# Relay.net
KiCad netlist of a schematic drawn in Altium Designer
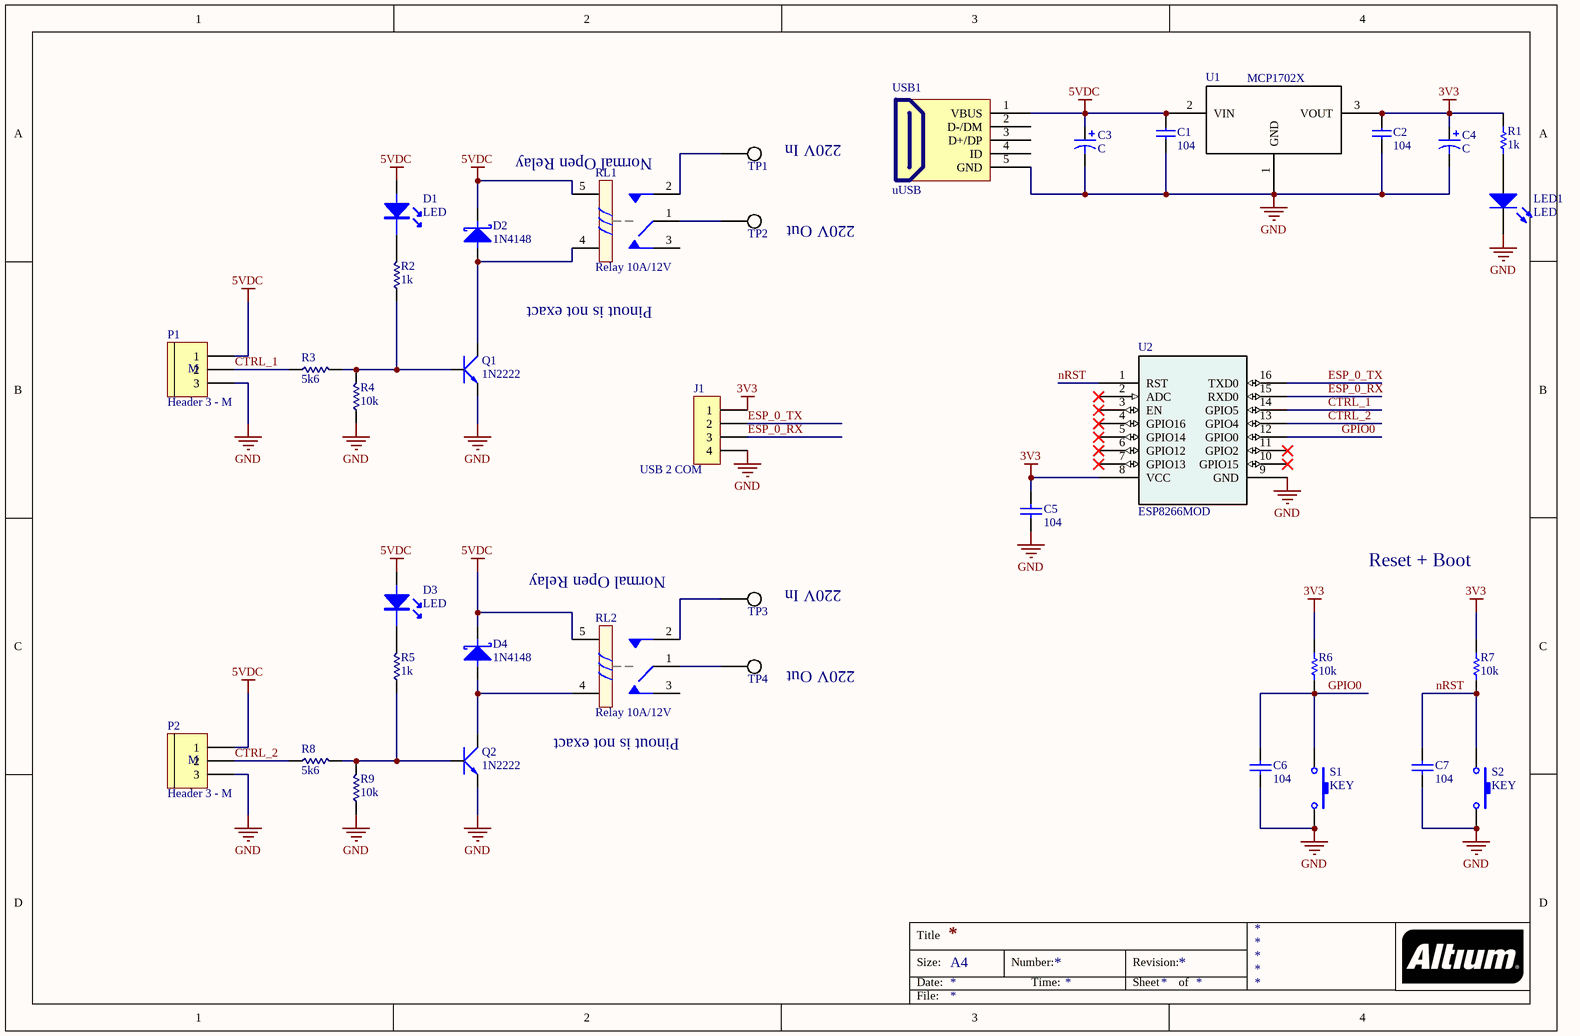
[diagram p0: Relay.SchDoc]

(export (version "E")
  (design (tool "Eeschema 10.0.6"))
  (components
    (comp (ref "C1")
      (value "104")
      (footprint "C0603")
      (description "Capacitor, X7R, ±10%")
      (fields (field (name "PART NUMBER") "C0402-1n0") (field (name "PUBLISHER") "Nordic Semiconductor"))
      (libsource (lib "Nordic Passive DB") (part "CAP"))
    )
    (comp (ref "C2")
      (value "104")
      (footprint "C0603")
      (description "Capacitor, X7R, ±10%")
      (fields (field (name "PART NUMBER") "C0402-1n0") (field (name "PUBLISHER") "Nordic Semiconductor"))
      (libsource (lib "Nordic Passive DB") (part "CAP"))
    )
    (comp (ref "C3")
      (value "C")
      (footprint "3216-18")
      (description "Cap 100uF/35V - 470uF/16V")
      (libsource (lib "Capacitor") (part "CAP POL"))
    )
    (comp (ref "C4")
      (value "C")
      (footprint "3216-18")
      (description "Cap 100uF/35V - 470uF/16V")
      (libsource (lib "Capacitor") (part "CAP POL"))
    )
    (comp (ref "C5")
      (value "104")
      (footprint "C0603")
      (description "Capacitor")
      (fields (field (name "PUBLISHER") "Altium Limited"))
      (libsource (lib "VTEKLib") (part "Cap Ceramic"))
    )
    (comp (ref "C6")
      (value "104")
      (footprint "C0603")
      (description "Capacitor")
      (fields (field (name "PUBLISHER") "Altium Limited"))
      (libsource (lib "VTEKLib") (part "Cap Ceramic"))
    )
    (comp (ref "C7")
      (value "104")
      (footprint "C0603")
      (description "Capacitor")
      (fields (field (name "PUBLISHER") "Altium Limited"))
      (libsource (lib "VTEKLib") (part "Cap Ceramic"))
    )
    (comp (ref "D1") (value "LED") (footprint "CAP10UF") (libsource (lib "Cty1") (part "LED")))
    (comp (ref "D2")
      (value "1N4148")
      (footprint "diode")
      (description "Schottky Diode")
      (libsource (lib "Cty1") (part "1N4148"))
    )
    (comp (ref "D3") (value "LED") (footprint "CAP10UF") (libsource (lib "Cty1") (part "LED")))
    (comp (ref "D4")
      (value "1N4148")
      (footprint "diode")
      (description "Schottky Diode")
      (libsource (lib "Cty1") (part "1N4148"))
    )
    (comp (ref "J1")
      (value "USB 2 COM")
      (footprint "HDR1X4")
      (description "Connector")
      (libsource (lib "Connecter") (part "CON4"))
    )
    (comp (ref "LED1")
      (value "LED")
      (footprint "LED0805")
      (description "Typical INFRARED GaAs LED")
      (fields (field (name "PUBLISHER") "Altium Limited"))
      (libsource (lib "VTEKLib") (part "LED"))
    )
    (comp (ref "P1")
      (value "Header 3 - M")
      (footprint "Medium - Header 3")
      (description "Header, 3-Pin, Medium")
      (fields (field (name "PUBLISHER") "Altium Limited"))
      (libsource (lib "Connecter") (part "Header 3 - M"))
    )
    (comp (ref "P2")
      (value "Header 3 - M")
      (footprint "Medium - Header 3")
      (description "Header, 3-Pin, Medium")
      (fields (field (name "PUBLISHER") "Altium Limited"))
      (libsource (lib "Connecter") (part "Header 3 - M"))
    )
    (comp (ref "Q1")
      (value "1N2222")
      (footprint "SOT23A")
      (description "NPN switching transistor  40V 600mA SOT23")
      (fields (field (name "MANUFACTURER") "Fairchild"))
      (libsource (lib "Cty1") (part "MMBT2222A"))
    )
    (comp (ref "Q2")
      (value "1N2222")
      (footprint "SOT23A")
      (description "NPN switching transistor  40V 600mA SOT23")
      (fields (field (name "MANUFACTURER") "Fairchild"))
      (libsource (lib "Cty1") (part "MMBT2222A"))
    )
    (comp (ref "R1")
      (value "1k")
      (footprint "R0603-2")
      (fields (field (name "PUBLISHER") "Altium Limited"))
      (libsource (lib "VTEKLib") (part "RES"))
    )
    (comp (ref "R2")
      (value "1k")
      (footprint "R1/4W")
      (description "Resistor 1/4W")
      (libsource (lib "Cty1") (part "R1/4W"))
    )
    (comp (ref "R3")
      (value "5k6")
      (footprint "R1/4W")
      (description "Resistor 1/4W")
      (libsource (lib "Cty1") (part "R1/4W"))
    )
    (comp (ref "R4")
      (value "10k")
      (footprint "R1/4W")
      (description "Resistor 1/4W")
      (libsource (lib "Cty1") (part "R1/4W"))
    )
    (comp (ref "R5")
      (value "1k")
      (footprint "R1/4W")
      (description "Resistor 1/4W")
      (libsource (lib "Cty1") (part "R1/4W"))
    )
    (comp (ref "R6")
      (value "10k")
      (footprint "R0603-2")
      (fields (field (name "PUBLISHER") "Altium Limited"))
      (libsource (lib "VTEKLib") (part "RES"))
    )
    (comp (ref "R7")
      (value "10k")
      (footprint "R0603-2")
      (fields (field (name "PUBLISHER") "Altium Limited"))
      (libsource (lib "VTEKLib") (part "RES"))
    )
    (comp (ref "R8")
      (value "5k6")
      (footprint "R1/4W")
      (description "Resistor 1/4W")
      (libsource (lib "Cty1") (part "R1/4W"))
    )
    (comp (ref "R9")
      (value "10k")
      (footprint "R1/4W")
      (description "Resistor 1/4W")
      (libsource (lib "Cty1") (part "R1/4W"))
    )
    (comp (ref "RL1")
      (value "Relay 10A/12V")
      (footprint "RL_SPDT_10A")
      (description "Relay SPDT,10A - 12VDC 5 Pin")
      (libsource (lib "Cty1") (part "Relay 1"))
    )
    (comp (ref "RL2")
      (value "Relay 10A/12V")
      (footprint "RL_SPDT_10A")
      (description "Relay SPDT,10A - 12VDC 5 Pin")
      (libsource (lib "Cty1") (part "Relay 1"))
    )
    (comp (ref "S1")
      (value "KEY")
      (footprint "SW-SMD")
      (description "Button")
      (libsource (lib "VTEKLib") (part "Button2"))
    )
    (comp (ref "S2")
      (value "KEY")
      (footprint "SW-SMD")
      (description "Button")
      (libsource (lib "VTEKLib") (part "Button2"))
    )
    (comp (ref "TP1")
      (value "TP?")
      (footprint "Test Point")
      (description "Test point")
      (libsource (lib "Cty1") (part "TP_"))
    )
    (comp (ref "TP2")
      (value "TP?")
      (footprint "Test Point")
      (description "Test point")
      (libsource (lib "Cty1") (part "TP_"))
    )
    (comp (ref "TP3")
      (value "TP?")
      (footprint "Test Point")
      (description "Test point")
      (libsource (lib "Cty1") (part "TP_"))
    )
    (comp (ref "TP4")
      (value "TP?")
      (footprint "Test Point")
      (description "Test point")
      (libsource (lib "Cty1") (part "TP_"))
    )
    (comp (ref "U1")
      (value "MCP1702X")
      (footprint "SOT-89_3MC")
      (description "250 mA Low Quiescent Current LDO Regulator")
      (libsource (lib "SMPS_IC") (part "MCP1702X"))
    )
    (comp (ref "U2")
      (value "ESP8266MOD")
      (footprint "ESP_7")
      (description "ESP8266 WIFI MODULE V7")
      (libsource (lib "uC") (part "ESP8266MOD"))
    )
    (comp (ref "USB1") (value "uUSB") (footprint "USB_MICRO_SMD") (libsource (lib "VTEKLib") (part "USB_M")))
  )
  (nets
    (net (code "1") (name "/CTRL_1") (class "Default")
      (node (ref "P1") (pin "2") (pinfunction "2_2") (pintype "passive"))
      (node (ref "R3") (pin "1") (pinfunction "1_1") (pintype "passive"))
      (node (ref "U2") (pin "14") (pinfunction "GPIO5_14") (pintype "bidirectional"))
    )
    (net (code "2") (name "/CTRL_2") (class "Default")
      (node (ref "P2") (pin "2") (pinfunction "2_2") (pintype "passive"))
      (node (ref "R8") (pin "1") (pinfunction "1_1") (pintype "passive"))
      (node (ref "U2") (pin "13") (pinfunction "GPIO4_13") (pintype "bidirectional"))
    )
    (net (code "3") (name "/ESP_0_RX") (class "Default")
      (node (ref "J1") (pin "3") (pinfunction "3_3") (pintype "passive"))
      (node (ref "U2") (pin "15") (pinfunction "RXD0_15") (pintype "bidirectional"))
    )
    (net (code "4") (name "/ESP_0_TX") (class "Default")
      (node (ref "J1") (pin "2") (pinfunction "2_2") (pintype "passive"))
      (node (ref "U2") (pin "16") (pinfunction "TXD0_16") (pintype "bidirectional"))
    )
    (net (code "5") (name "/GPIO0") (class "Default")
      (node (ref "C6") (pin "2") (pinfunction "2_2") (pintype "passive"))
      (node (ref "R6") (pin "2") (pinfunction "2_2") (pintype "passive"))
      (node (ref "S1") (pin "1") (pinfunction "1_1") (pintype "passive"))
      (node (ref "U2") (pin "12") (pinfunction "GPIO0_12") (pintype "bidirectional"))
    )
    (net (code "6") (name "/nRST") (class "Default")
      (node (ref "C7") (pin "2") (pinfunction "2_2") (pintype "passive"))
      (node (ref "R7") (pin "2") (pinfunction "2_2") (pintype "passive"))
      (node (ref "S2") (pin "1") (pinfunction "1_1") (pintype "passive"))
      (node (ref "U2") (pin "1") (pinfunction "RST_1") (pintype "power_in"))
    )
    (net (code "7") (name "3V3") (class "Default")
      (node (ref "C2") (pin "1") (pinfunction "1_1") (pintype "passive"))
      (node (ref "C4") (pin "1") (pinfunction "1_1") (pintype "passive"))
      (node (ref "C5") (pin "1") (pinfunction "1_1") (pintype "passive"))
      (node (ref "J1") (pin "1") (pinfunction "1_1") (pintype "passive"))
      (node (ref "R1") (pin "1") (pinfunction "1_1") (pintype "passive"))
      (node (ref "R6") (pin "1") (pinfunction "1_1") (pintype "passive"))
      (node (ref "R7") (pin "1") (pinfunction "1_1") (pintype "passive"))
      (node (ref "U1") (pin "3") (pinfunction "VOUT_3") (pintype "passive"))
      (node (ref "U2") (pin "8") (pinfunction "VCC_8") (pintype "power_in"))
    )
    (net (code "8") (name "5VDC") (class "Default")
      (node (ref "C1") (pin "1") (pinfunction "1_1") (pintype "passive"))
      (node (ref "C3") (pin "1") (pinfunction "1_1") (pintype "passive"))
      (node (ref "D1") (pin "1") (pinfunction "1_1") (pintype "passive"))
      (node (ref "D2") (pin "2") (pinfunction "K_2") (pintype "passive"))
      (node (ref "D3") (pin "1") (pinfunction "1_1") (pintype "passive"))
      (node (ref "D4") (pin "2") (pinfunction "K_2") (pintype "passive"))
      (node (ref "P1") (pin "1") (pinfunction "1_1") (pintype "passive"))
      (node (ref "P2") (pin "1") (pinfunction "1_1") (pintype "passive"))
      (node (ref "RL1") (pin "5") (pinfunction "5_5") (pintype "passive"))
      (node (ref "RL2") (pin "5") (pinfunction "5_5") (pintype "passive"))
      (node (ref "U1") (pin "2") (pinfunction "VIN_2") (pintype "passive"))
      (node (ref "USB1") (pin "1") (pinfunction "VBUS_1") (pintype "passive"))
    )
    (net (code "9") (name "GND") (class "Default")
      (node (ref "C1") (pin "2") (pinfunction "2_2") (pintype "passive"))
      (node (ref "C2") (pin "2") (pinfunction "2_2") (pintype "passive"))
      (node (ref "C3") (pin "2") (pinfunction "2_2") (pintype "passive"))
      (node (ref "C4") (pin "2") (pinfunction "2_2") (pintype "passive"))
      (node (ref "C5") (pin "2") (pinfunction "2_2") (pintype "passive"))
      (node (ref "C6") (pin "1") (pinfunction "1_1") (pintype "passive"))
      (node (ref "C7") (pin "1") (pinfunction "1_1") (pintype "passive"))
      (node (ref "J1") (pin "4") (pinfunction "4_4") (pintype "passive"))
      (node (ref "LED1") (pin "2") (pinfunction "K_2") (pintype "passive"))
      (node (ref "P1") (pin "3") (pinfunction "3_3") (pintype "passive"))
      (node (ref "P2") (pin "3") (pinfunction "3_3") (pintype "passive"))
      (node (ref "Q1") (pin "2") (pinfunction "E_2") (pintype "passive"))
      (node (ref "Q2") (pin "2") (pinfunction "E_2") (pintype "passive"))
      (node (ref "R4") (pin "1") (pinfunction "1_1") (pintype "passive"))
      (node (ref "R9") (pin "1") (pinfunction "1_1") (pintype "passive"))
      (node (ref "S1") (pin "2") (pinfunction "2_2") (pintype "passive"))
      (node (ref "S2") (pin "2") (pinfunction "2_2") (pintype "passive"))
      (node (ref "U1") (pin "1") (pinfunction "GND_1") (pintype "passive"))
      (node (ref "U2") (pin "9") (pinfunction "GND_9") (pintype "power_in"))
      (node (ref "USB1") (pin "5") (pinfunction "GND_5") (pintype "passive"))
    )
    (net (code "10") (name "Net-(D1-Pad2)") (class "Default")
      (node (ref "D1") (pin "2") (pinfunction "2_2") (pintype "passive"))
      (node (ref "R2") (pin "2") (pinfunction "2_2") (pintype "passive"))
    )
    (net (code "11") (name "Net-(D2-A)") (class "Default")
      (node (ref "D2") (pin "1") (pinfunction "A_1") (pintype "passive"))
      (node (ref "Q1") (pin "3") (pinfunction "C_3") (pintype "passive"))
      (node (ref "RL1") (pin "4") (pinfunction "4_4") (pintype "passive"))
    )
    (net (code "12") (name "Net-(D3-Pad2)") (class "Default")
      (node (ref "D3") (pin "2") (pinfunction "2_2") (pintype "passive"))
      (node (ref "R5") (pin "2") (pinfunction "2_2") (pintype "passive"))
    )
    (net (code "13") (name "Net-(D4-A)") (class "Default")
      (node (ref "D4") (pin "1") (pinfunction "A_1") (pintype "passive"))
      (node (ref "Q2") (pin "3") (pinfunction "C_3") (pintype "passive"))
      (node (ref "RL2") (pin "4") (pinfunction "4_4") (pintype "passive"))
    )
    (net (code "14") (name "Net-(LED1-A)") (class "Default")
      (node (ref "LED1") (pin "1") (pinfunction "A_1") (pintype "passive"))
      (node (ref "R1") (pin "2") (pinfunction "2_2") (pintype "passive"))
    )
    (net (code "15") (name "Net-(Q1-B)") (class "Default")
      (node (ref "Q1") (pin "1") (pinfunction "B_1") (pintype "passive"))
      (node (ref "R2") (pin "1") (pinfunction "1_1") (pintype "passive"))
      (node (ref "R3") (pin "2") (pinfunction "2_2") (pintype "passive"))
      (node (ref "R4") (pin "2") (pinfunction "2_2") (pintype "passive"))
    )
    (net (code "16") (name "Net-(Q2-B)") (class "Default")
      (node (ref "Q2") (pin "1") (pinfunction "B_1") (pintype "passive"))
      (node (ref "R5") (pin "1") (pinfunction "1_1") (pintype "passive"))
      (node (ref "R8") (pin "2") (pinfunction "2_2") (pintype "passive"))
      (node (ref "R9") (pin "2") (pinfunction "2_2") (pintype "passive"))
    )
    (net (code "17") (name "Net-(RL1-Pad1)") (class "Default")
      (node (ref "RL1") (pin "1") (pinfunction "1_1") (pintype "passive"))
      (node (ref "TP2") (pin "1") (pinfunction "1_1") (pintype "passive"))
    )
    (net (code "18") (name "Net-(RL1-Pad2)") (class "Default")
      (node (ref "RL1") (pin "2") (pinfunction "2_2") (pintype "passive"))
      (node (ref "TP1") (pin "1") (pinfunction "1_1") (pintype "passive"))
    )
    (net (code "19") (name "Net-(RL2-Pad1)") (class "Default")
      (node (ref "RL2") (pin "1") (pinfunction "1_1") (pintype "passive"))
      (node (ref "TP4") (pin "1") (pinfunction "1_1") (pintype "passive"))
    )
    (net (code "20") (name "Net-(RL2-Pad2)") (class "Default")
      (node (ref "RL2") (pin "2") (pinfunction "2_2") (pintype "passive"))
      (node (ref "TP3") (pin "1") (pinfunction "1_1") (pintype "passive"))
    )
    (net (code "21") (name "unconnected-(RL1-Pad3)") (class "Default")
      (node (ref "RL1") (pin "3") (pinfunction "3_3") (pintype "passive"))
    )
    (net (code "22") (name "unconnected-(RL2-Pad3)") (class "Default")
      (node (ref "RL2") (pin "3") (pinfunction "3_3") (pintype "passive"))
    )
    (net (code "23") (name "unconnected-(U2-ADC-Pad2)") (class "Default")
      (node (ref "U2") (pin "2") (pinfunction "ADC_2") (pintype "input+no_connect"))
    )
    (net (code "24") (name "unconnected-(U2-EN-Pad3)") (class "Default")
      (node (ref "U2") (pin "3") (pinfunction "EN_3") (pintype "bidirectional+no_connect"))
    )
    (net (code "25") (name "unconnected-(U2-GPIO2-Pad11)") (class "Default")
      (node (ref "U2") (pin "11") (pinfunction "GPIO2_11") (pintype "bidirectional+no_connect"))
    )
    (net (code "26") (name "unconnected-(U2-GPIO12-Pad6)") (class "Default")
      (node (ref "U2") (pin "6") (pinfunction "GPIO12_6") (pintype "bidirectional+no_connect"))
    )
    (net (code "27") (name "unconnected-(U2-GPIO13-Pad7)") (class "Default")
      (node (ref "U2") (pin "7") (pinfunction "GPIO13_7") (pintype "bidirectional+no_connect"))
    )
    (net (code "28") (name "unconnected-(U2-GPIO14-Pad5)") (class "Default")
      (node (ref "U2") (pin "5") (pinfunction "GPIO14_5") (pintype "bidirectional+no_connect"))
    )
    (net (code "29") (name "unconnected-(U2-GPIO15-Pad10)") (class "Default")
      (node (ref "U2") (pin "10") (pinfunction "GPIO15_10") (pintype "bidirectional+no_connect"))
    )
    (net (code "30") (name "unconnected-(U2-GPIO16-Pad4)") (class "Default")
      (node (ref "U2") (pin "4") (pinfunction "GPIO16_4") (pintype "bidirectional+no_connect"))
    )
    (net (code "31") (name "unconnected-(USB1-D+{slash}DP-Pad3)") (class "Default")
      (node (ref "USB1") (pin "3") (pinfunction "D+/DP_3") (pintype "passive"))
    )
    (net (code "32") (name "unconnected-(USB1-D-{slash}DM-Pad2)") (class "Default")
      (node (ref "USB1") (pin "2") (pinfunction "D-/DM_2") (pintype "passive"))
    )
    (net (code "33") (name "unconnected-(USB1-ID-Pad4)") (class "Default")
      (node (ref "USB1") (pin "4") (pinfunction "ID_4") (pintype "passive"))
    )
  )
)
